# entr_e_sortie.net
KiCad netlist of a schematic drawn in Altium Designer
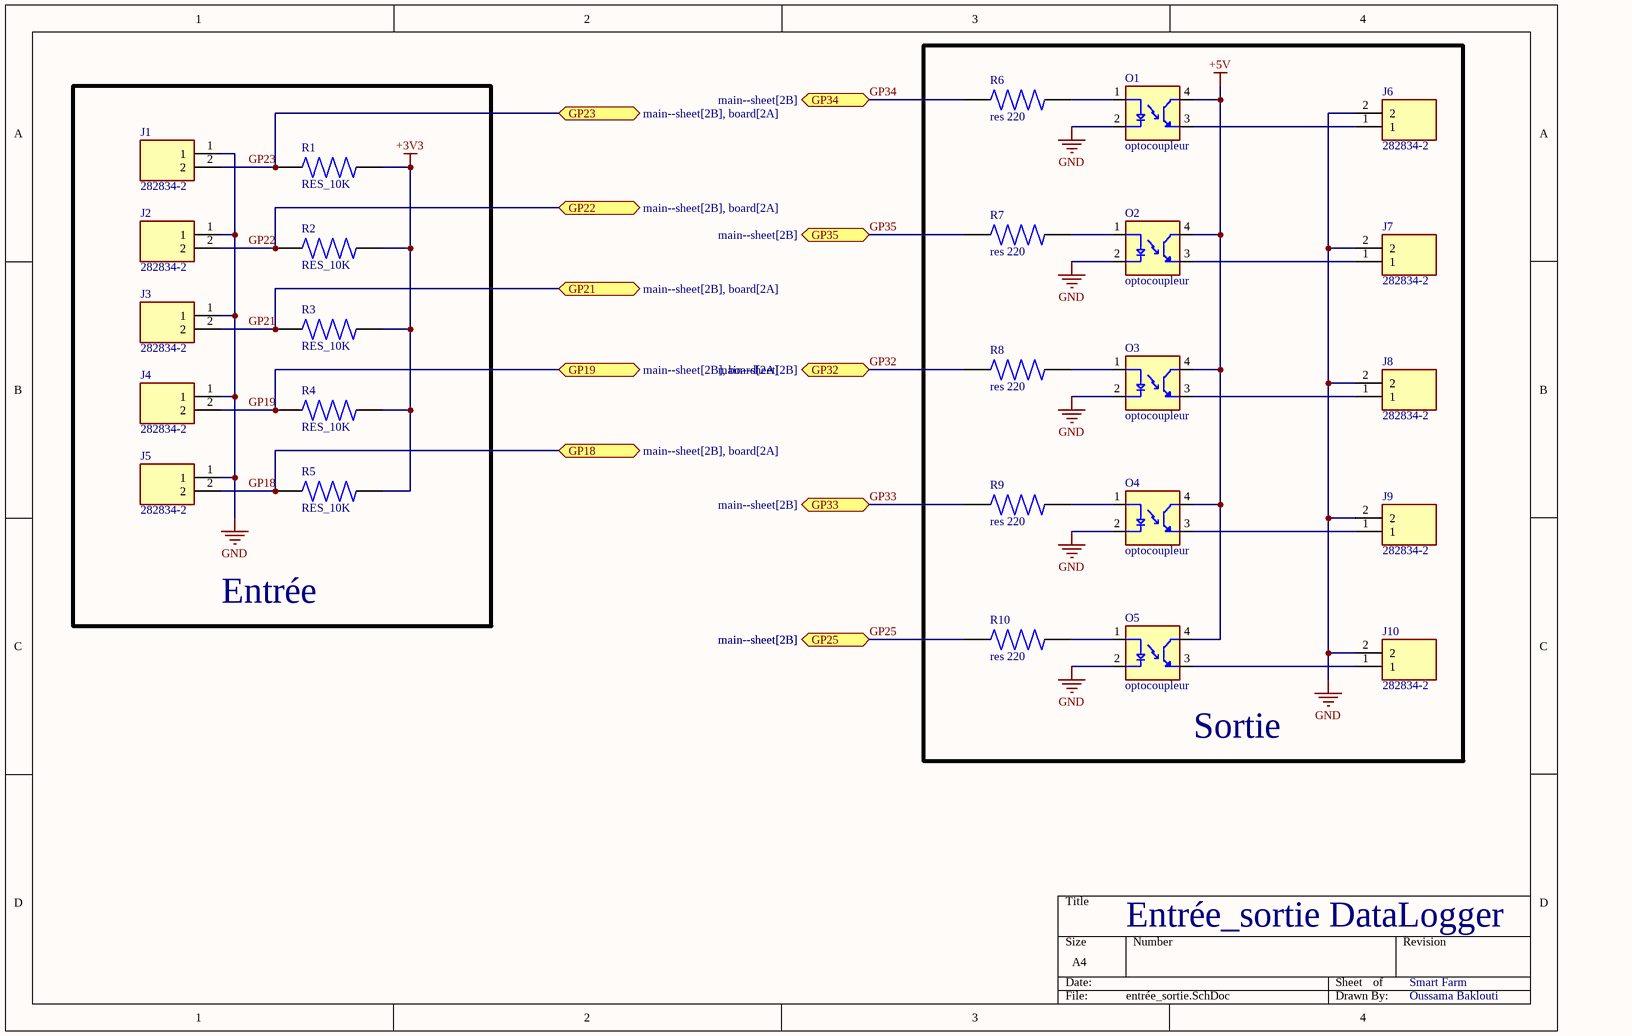
[diagram p0: entrée_sortie.SchDoc]

(export (version "E")
  (design (tool "Eeschema 10.0.6"))
  (components
    (comp (ref "J1")
      (value "282834-2")
      (footprint "282834-2")
      (fields (field (name "MF") "{'manufacturer': u'TE Connectivity'}"))
      (libsource (lib "282834-2") (part "282834-2"))
    )
    (comp (ref "J2")
      (value "282834-2")
      (footprint "282834-2")
      (fields (field (name "MF") "{'manufacturer': u'TE Connectivity'}"))
      (libsource (lib "282834-2") (part "282834-2"))
    )
    (comp (ref "J3")
      (value "282834-2")
      (footprint "282834-2")
      (fields (field (name "MF") "{'manufacturer': u'TE Connectivity'}"))
      (libsource (lib "282834-2") (part "282834-2"))
    )
    (comp (ref "J4")
      (value "282834-2")
      (footprint "282834-2")
      (fields (field (name "MF") "{'manufacturer': u'TE Connectivity'}"))
      (libsource (lib "282834-2") (part "282834-2"))
    )
    (comp (ref "J5")
      (value "282834-2")
      (footprint "282834-2")
      (fields (field (name "MF") "{'manufacturer': u'TE Connectivity'}"))
      (libsource (lib "282834-2") (part "282834-2"))
    )
    (comp (ref "J6")
      (value "282834-2")
      (footprint "282834-2")
      (fields (field (name "MF") "{'manufacturer': u'TE Connectivity'}"))
      (libsource (lib "") (part "282834-2_1"))
    )
    (comp (ref "J7")
      (value "282834-2")
      (footprint "282834-2")
      (fields (field (name "MF") "{'manufacturer': u'TE Connectivity'}"))
      (libsource (lib "") (part "282834-2_1"))
    )
    (comp (ref "J8")
      (value "282834-2")
      (footprint "282834-2")
      (fields (field (name "MF") "{'manufacturer': u'TE Connectivity'}"))
      (libsource (lib "") (part "282834-2_1"))
    )
    (comp (ref "J9")
      (value "282834-2")
      (footprint "282834-2")
      (fields (field (name "MF") "{'manufacturer': u'TE Connectivity'}"))
      (libsource (lib "") (part "282834-2_1"))
    )
    (comp (ref "J10")
      (value "282834-2")
      (footprint "282834-2")
      (fields (field (name "MF") "{'manufacturer': u'TE Connectivity'}"))
      (libsource (lib "") (part "282834-2_1"))
    )
    (comp (ref "O1")
      (value "optocoupleur")
      (footprint "optocoupleur")
      (libsource (lib "Data_logger") (part "optocoupleur"))
    )
    (comp (ref "O2")
      (value "optocoupleur")
      (footprint "optocoupleur")
      (libsource (lib "Data_logger") (part "optocoupleur"))
    )
    (comp (ref "O3")
      (value "optocoupleur")
      (footprint "optocoupleur")
      (libsource (lib "Data_logger") (part "optocoupleur"))
    )
    (comp (ref "O4")
      (value "optocoupleur")
      (footprint "optocoupleur")
      (libsource (lib "Data_logger") (part "optocoupleur"))
    )
    (comp (ref "O5")
      (value "optocoupleur")
      (footprint "optocoupleur")
      (libsource (lib "Data_logger") (part "optocoupleur"))
    )
    (comp (ref "R1") (value "RES_10K") (footprint "RES_10k") (libsource (lib "Data_logger") (part "RES_10K")))
    (comp (ref "R2") (value "RES_10K") (footprint "RES_10k") (libsource (lib "Data_logger") (part "RES_10K")))
    (comp (ref "R3") (value "RES_10K") (footprint "RES_10k") (libsource (lib "Data_logger") (part "RES_10K")))
    (comp (ref "R4") (value "RES_10K") (footprint "RES_10k") (libsource (lib "Data_logger") (part "RES_10K")))
    (comp (ref "R5") (value "RES_10K") (footprint "RES_10k") (libsource (lib "Data_logger") (part "RES_10K")))
    (comp (ref "R6") (value "res 220") (footprint "res 220") (libsource (lib "Data_logger") (part "res 220")))
    (comp (ref "R7") (value "res 220") (footprint "res 220") (libsource (lib "Data_logger") (part "res 220")))
    (comp (ref "R8") (value "res 220") (footprint "res 220") (libsource (lib "Data_logger") (part "res 220")))
    (comp (ref "R9") (value "res 220") (footprint "res 220") (libsource (lib "Data_logger") (part "res 220")))
    (comp (ref "R10")
      (value "res 220")
      (footprint "res 220")
      (libsource (lib "Data_logger") (part "res 220"))
    )
  )
  (nets
    (net (code "1") (name "+3V3") (class "Default")
      (node (ref "R1") (pin "2") (pinfunction "2_2") (pintype "passive"))
      (node (ref "R2") (pin "2") (pinfunction "2_2") (pintype "passive"))
      (node (ref "R3") (pin "2") (pinfunction "2_2") (pintype "passive"))
      (node (ref "R4") (pin "2") (pinfunction "2_2") (pintype "passive"))
      (node (ref "R5") (pin "2") (pinfunction "2_2") (pintype "passive"))
    )
    (net (code "2") (name "+5V") (class "Default")
      (node (ref "O1") (pin "4") (pinfunction "CT_4") (pintype "passive"))
      (node (ref "O2") (pin "4") (pinfunction "CT_4") (pintype "passive"))
      (node (ref "O3") (pin "4") (pinfunction "CT_4") (pintype "passive"))
      (node (ref "O4") (pin "4") (pinfunction "CT_4") (pintype "passive"))
      (node (ref "O5") (pin "4") (pinfunction "CT_4") (pintype "passive"))
    )
    (net (code "3") (name "/GP18") (class "Default")
      (node (ref "J5") (pin "2") (pinfunction "2_2") (pintype "passive"))
      (node (ref "R5") (pin "1") (pinfunction "1_1") (pintype "passive"))
    )
    (net (code "4") (name "/GP19") (class "Default")
      (node (ref "J4") (pin "2") (pinfunction "2_2") (pintype "passive"))
      (node (ref "R4") (pin "1") (pinfunction "1_1") (pintype "passive"))
    )
    (net (code "5") (name "/GP21") (class "Default")
      (node (ref "J3") (pin "2") (pinfunction "2_2") (pintype "passive"))
      (node (ref "R3") (pin "1") (pinfunction "1_1") (pintype "passive"))
    )
    (net (code "6") (name "/GP22") (class "Default")
      (node (ref "J2") (pin "2") (pinfunction "2_2") (pintype "passive"))
      (node (ref "R2") (pin "1") (pinfunction "1_1") (pintype "passive"))
    )
    (net (code "7") (name "/GP23") (class "Default")
      (node (ref "J1") (pin "2") (pinfunction "2_2") (pintype "passive"))
      (node (ref "R1") (pin "1") (pinfunction "1_1") (pintype "passive"))
    )
    (net (code "8") (name "/GP25") (class "Default")
      (node (ref "R10") (pin "1") (pinfunction "1_1") (pintype "passive"))
    )
    (net (code "9") (name "/GP32") (class "Default")
      (node (ref "R8") (pin "1") (pinfunction "1_1") (pintype "passive"))
    )
    (net (code "10") (name "/GP33") (class "Default")
      (node (ref "R9") (pin "1") (pinfunction "1_1") (pintype "passive"))
    )
    (net (code "11") (name "/GP34") (class "Default")
      (node (ref "R6") (pin "1") (pinfunction "1_1") (pintype "passive"))
    )
    (net (code "12") (name "/GP35") (class "Default")
      (node (ref "R7") (pin "1") (pinfunction "1_1") (pintype "passive"))
    )
    (net (code "13") (name "GND") (class "Default")
      (node (ref "J1") (pin "1") (pinfunction "1_1") (pintype "passive"))
      (node (ref "J10") (pin "2") (pinfunction "2_2") (pintype "passive"))
      (node (ref "J2") (pin "1") (pinfunction "1_1") (pintype "passive"))
      (node (ref "J3") (pin "1") (pinfunction "1_1") (pintype "passive"))
      (node (ref "J4") (pin "1") (pinfunction "1_1") (pintype "passive"))
      (node (ref "J5") (pin "1") (pinfunction "1_1") (pintype "passive"))
      (node (ref "J6") (pin "2") (pinfunction "2_2") (pintype "passive"))
      (node (ref "J7") (pin "2") (pinfunction "2_2") (pintype "passive"))
      (node (ref "J8") (pin "2") (pinfunction "2_2") (pintype "passive"))
      (node (ref "J9") (pin "2") (pinfunction "2_2") (pintype "passive"))
      (node (ref "O1") (pin "2") (pinfunction "C_2") (pintype "passive"))
      (node (ref "O2") (pin "2") (pinfunction "C_2") (pintype "passive"))
      (node (ref "O3") (pin "2") (pinfunction "C_2") (pintype "passive"))
      (node (ref "O4") (pin "2") (pinfunction "C_2") (pintype "passive"))
      (node (ref "O5") (pin "2") (pinfunction "C_2") (pintype "passive"))
    )
    (net (code "14") (name "Net-(O1-A)") (class "Default")
      (node (ref "O1") (pin "1") (pinfunction "A_1") (pintype "passive"))
      (node (ref "R6") (pin "2") (pinfunction "2_2") (pintype "passive"))
    )
    (net (code "15") (name "Net-(O1-ET)") (class "Default")
      (node (ref "J6") (pin "1") (pinfunction "1_1") (pintype "passive"))
      (node (ref "O1") (pin "3") (pinfunction "ET_3") (pintype "passive"))
    )
    (net (code "16") (name "Net-(O2-A)") (class "Default")
      (node (ref "O2") (pin "1") (pinfunction "A_1") (pintype "passive"))
      (node (ref "R7") (pin "2") (pinfunction "2_2") (pintype "passive"))
    )
    (net (code "17") (name "Net-(O2-ET)") (class "Default")
      (node (ref "J7") (pin "1") (pinfunction "1_1") (pintype "passive"))
      (node (ref "O2") (pin "3") (pinfunction "ET_3") (pintype "passive"))
    )
    (net (code "18") (name "Net-(O3-A)") (class "Default")
      (node (ref "O3") (pin "1") (pinfunction "A_1") (pintype "passive"))
      (node (ref "R8") (pin "2") (pinfunction "2_2") (pintype "passive"))
    )
    (net (code "19") (name "Net-(O3-ET)") (class "Default")
      (node (ref "J8") (pin "1") (pinfunction "1_1") (pintype "passive"))
      (node (ref "O3") (pin "3") (pinfunction "ET_3") (pintype "passive"))
    )
    (net (code "20") (name "Net-(O4-A)") (class "Default")
      (node (ref "O4") (pin "1") (pinfunction "A_1") (pintype "passive"))
      (node (ref "R9") (pin "2") (pinfunction "2_2") (pintype "passive"))
    )
    (net (code "21") (name "Net-(O4-ET)") (class "Default")
      (node (ref "J9") (pin "1") (pinfunction "1_1") (pintype "passive"))
      (node (ref "O4") (pin "3") (pinfunction "ET_3") (pintype "passive"))
    )
    (net (code "22") (name "Net-(O5-A)") (class "Default")
      (node (ref "O5") (pin "1") (pinfunction "A_1") (pintype "passive"))
      (node (ref "R10") (pin "2") (pinfunction "2_2") (pintype "passive"))
    )
    (net (code "23") (name "Net-(O5-ET)") (class "Default")
      (node (ref "J10") (pin "1") (pinfunction "1_1") (pintype "passive"))
      (node (ref "O5") (pin "3") (pinfunction "ET_3") (pintype "passive"))
    )
  )
)
